# task1_sh1.net
KiCad netlist of a schematic drawn in Altium Designer
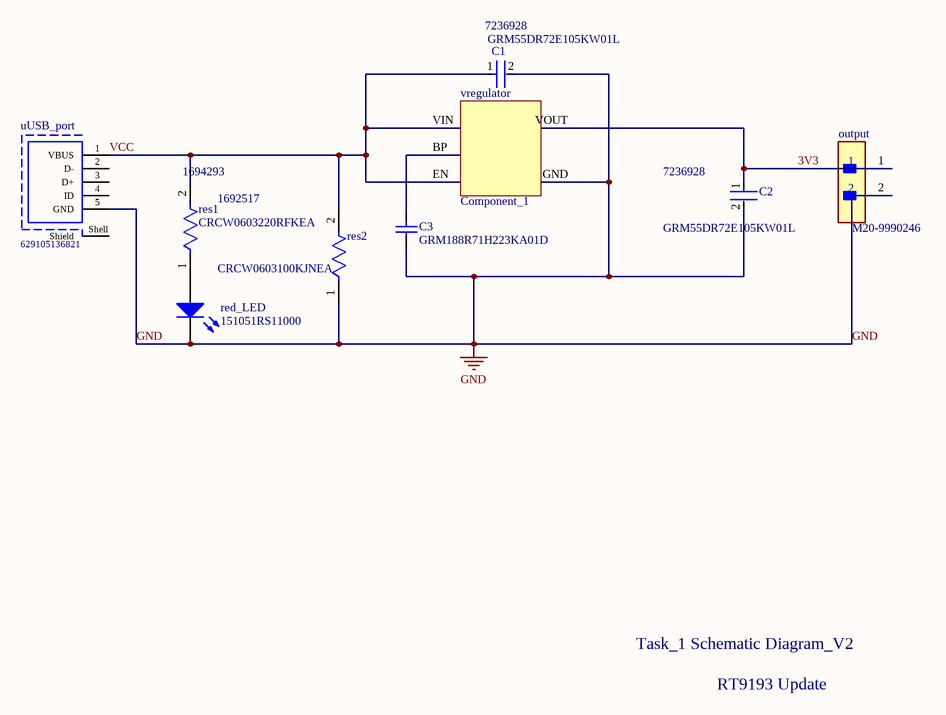
[diagram p0: task1_sh1.SchDoc]

(export (version "E")
  (design (tool "Eeschema 10.0.6"))
  (components
    (comp (ref "C1")
      (value "GRM55DR72E105KW01L")
      (footprint "FP-GRM55D-0_4-IPC_A")
      (description "Chip Multilayer Ceramic Capacitors for General Purpose, 2220, 1.0uF, X7R, 15%, 10%, 250V")
      (fields
        (field (name "VOLTAGE") "250V")
        (field (name "TOLERANCE") "10%")
        (field (name "SUPPLIER PART NUMBER 1") "7236928")
      )
      (libsource (lib "Altium Content Vault") (part "b4654b650e69147ec39a6b967a45e02"))
    )
    (comp (ref "C2")
      (value "GRM55DR72E105KW01L")
      (footprint "FP-GRM55D-0_4-IPC_A")
      (description "Chip Multilayer Ceramic Capacitors for General Purpose, 2220, 1.0uF, X7R, 15%, 10%, 250V")
      (fields
        (field (name "VOLTAGE") "250V")
        (field (name "TOLERANCE") "10%")
        (field (name "SUPPLIER PART NUMBER 1") "7236928")
      )
      (libsource (lib "Altium Content Vault") (part "b4654b650e69147ec39a6b967a45e02"))
    )
    (comp (ref "C3")
      (value "GRM188R71H223KA01D")
      (footprint "CAPC1608X90X35ML10T15")
      (fields (field (name "MANUFACTURER") "Murata"))
      (libsource (lib "Altium Content Vault") (part "CAP"))
    )
    (comp (ref "output")
      (value "M20-9990246")
      (footprint "FP-M20-9990246-MFG")
      (description "CONN HEADER VERT 2POS 2.54MM")
      (fields
        (field (name "OCTOPART") "https://octopart.com/m20-9990246-harwin-2590635")
        (field (name "MANUFACTURER") "Harwin")
      )
      (libsource (lib "Altium Content Vault") (part "3bc925449376181038e59eaffc5286c"))
    )
    (comp (ref "red_LED")
      (value "151051RS11000")
      (footprint "Type 5mm")
      (description "THT LED round mono-color color lens, WL-TMRW, Red")
      (fields (field (name "MANUFACTURER") "Wuerth Elektronik"))
      (libsource (lib "Altium Content Vault") (part "WE-LED_K1A2-2"))
    )
    (comp (ref "res1")
      (value "CRCW0603220RFKEA")
      (footprint "FP-CRCW0603-e3-MFG")
      (description "RES Thick Film, 220Ω, 1%, 0.1W, 100ppm/°C, 0603")
      (fields (field (name "TOLERANCE") "1%") (field (name "SUPPLIER PART NUMBER 1") "1694293"))
      (libsource (lib "Altium Content Vault") (part "1029c3af85768c4190bb7ad29bc67b5"))
    )
    (comp (ref "res2")
      (value "CRCW0603100KJNEA")
      (footprint "FP-CRCW0603-e3-IPC_C")
      (description "RES Thick Film, 100kΩ, 5%, 0.1W, 200ppm/°C, 0603")
      (fields (field (name "TOLERANCE") "5%") (field (name "SUPPLIER PART NUMBER 1") "1692517"))
      (libsource (lib "Altium Content Vault") (part "1029c3af85768c4190bb7ad29bc67b5"))
    )
    (comp (ref "uUSB_port")
      (value "629105136821")
      (footprint "629105136821")
      (description "Micro USB 2.0 Type B Receptacle WR-COM, Horizontal, SMT, with Pads and Pegs")
      (fields (field (name "MANUFACTURER") "Wurth Elektronik") (field (name "PUBLISHER") "WurthElektronik"))
      (libsource (lib "Altium Content Vault") (part "WE-USB-5-1SHLD"))
    )
    (comp (ref "vregulator")
      (value "Component_1")
      (footprint "9193new")
      (libsource (lib "rt9193new") (part "Component_1"))
    )
  )
  (nets
    (net (code "1") (name "/3V3") (class "Default")
      (node (ref "C2") (pin "1") (pinfunction "1_1") (pintype "passive"))
      (node (ref "output") (pin "1") (pinfunction "1_1") (pintype "passive"))
      (node (ref "vregulator") (pin "VOUT") (pintype "power_in"))
    )
    (net (code "2") (name "/VCC") (class "Default")
      (node (ref "C1") (pin "1") (pinfunction "1_1") (pintype "passive"))
      (node (ref "res1") (pin "2") (pinfunction "2_2") (pintype "passive"))
      (node (ref "res2") (pin "2") (pinfunction "2_2") (pintype "passive"))
      (node (ref "uUSB_port") (pin "1") (pinfunction "VBUS_1") (pintype "passive"))
      (node (ref "vregulator") (pin "EN") (pintype "power_in"))
      (node (ref "vregulator") (pin "VIN") (pintype "power_in"))
    )
    (net (code "3") (name "GND") (class "Default")
      (node (ref "C1") (pin "2") (pinfunction "2_2") (pintype "passive"))
      (node (ref "C2") (pin "2") (pinfunction "2_2") (pintype "passive"))
      (node (ref "C3") (pin "1") (pinfunction "1_1") (pintype "passive"))
      (node (ref "output") (pin "2") (pinfunction "2_2") (pintype "passive"))
      (node (ref "red_LED") (pin "1") (pinfunction "K_1") (pintype "passive"))
      (node (ref "res2") (pin "1") (pinfunction "1_1") (pintype "passive"))
      (node (ref "uUSB_port") (pin "5") (pinfunction "GND_5") (pintype "passive"))
      (node (ref "vregulator") (pin "GND") (pintype "power_in"))
    )
    (net (code "4") (name "Net-(C3-Pad2)") (class "Default")
      (node (ref "C3") (pin "2") (pinfunction "2_2") (pintype "passive"))
      (node (ref "vregulator") (pin "BP") (pintype "power_in"))
    )
    (net (code "5") (name "Net-(red_LED-A)") (class "Default")
      (node (ref "red_LED") (pin "2") (pinfunction "A_2") (pintype "passive"))
      (node (ref "res1") (pin "1") (pinfunction "1_1") (pintype "passive"))
    )
    (net (code "6") (name "unconnected-(uUSB_port-D+-Pad3)") (class "Default")
      (node (ref "uUSB_port") (pin "3") (pinfunction "D+_3") (pintype "passive"))
    )
    (net (code "7") (name "unconnected-(uUSB_port-D--Pad2)") (class "Default")
      (node (ref "uUSB_port") (pin "2") (pinfunction "D-_2") (pintype "passive"))
    )
    (net (code "8") (name "unconnected-(uUSB_port-ID-Pad4)") (class "Default")
      (node (ref "uUSB_port") (pin "4") (pinfunction "ID_4") (pintype "passive"))
    )
    (net (code "9") (name "unconnected-(uUSB_port-Shield-PadShell)") (class "Default")
      (node (ref "uUSB_port") (pin "Shell") (pinfunction "Shield_Shell") (pintype "passive"))
    )
  )
)
